# Sheet1.net
KiCad netlist of a schematic drawn in Altium Designer
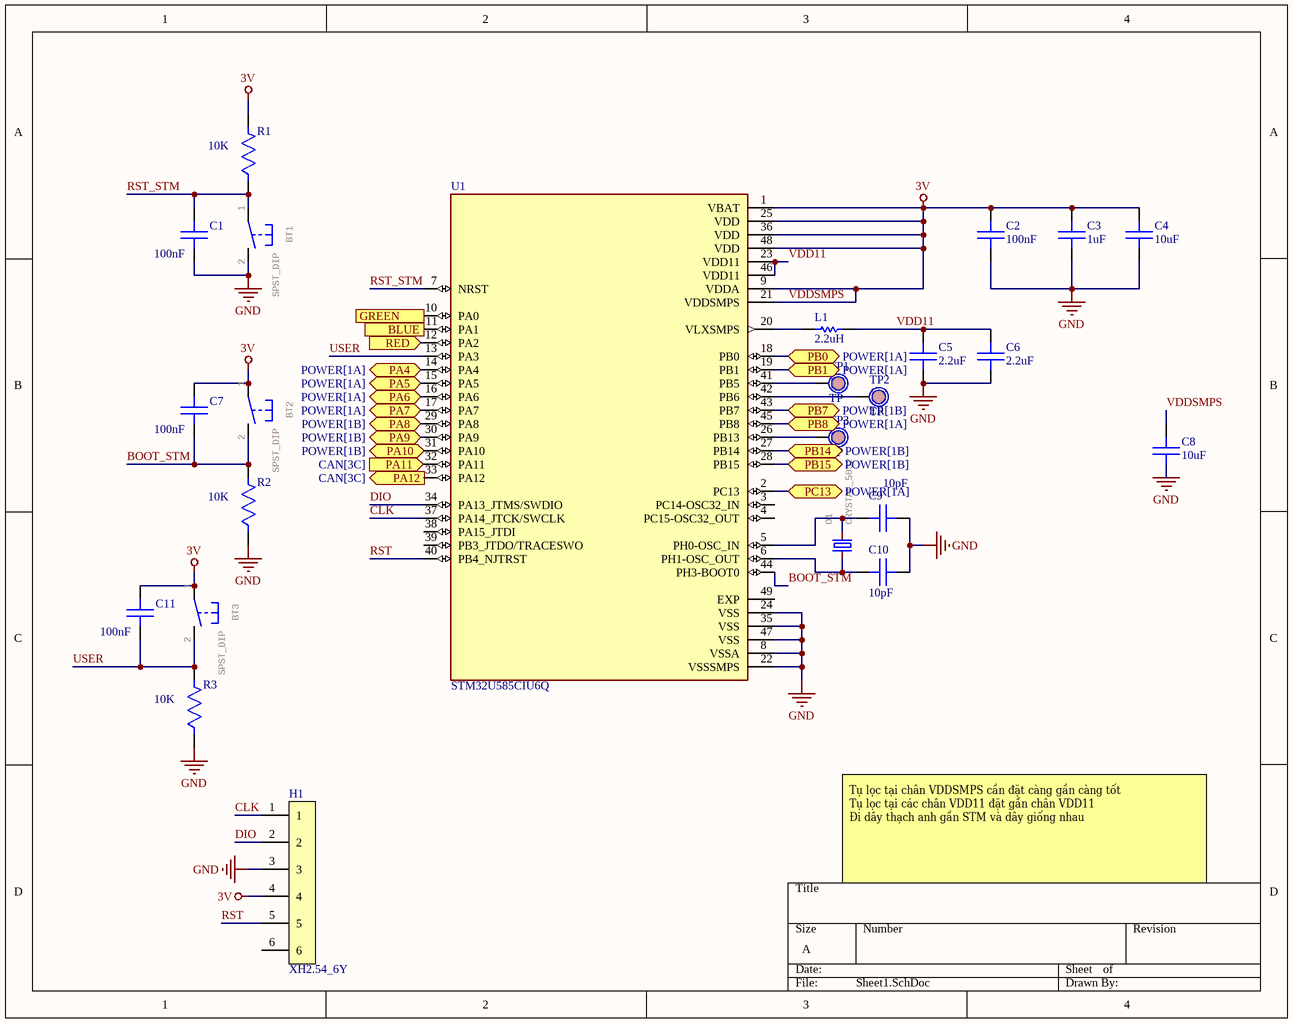
[diagram p0: Sheet1.SchDoc]

(export (version "E")
  (design (tool "Eeschema 10.0.6"))
  (components
    (comp (ref "BT1")
      (value "SPST_DIP")
      (footprint "SPST_BUTTON_2DIP")
      (libsource (lib "IoTVision_Library") (part "SPST_DIP"))
    )
    (comp (ref "BT2")
      (value "SPST_DIP")
      (footprint "SPST_BUTTON_2DIP")
      (libsource (lib "IoTVision_Library") (part "SPST_DIP"))
    )
    (comp (ref "BT3")
      (value "SPST_DIP")
      (footprint "SPST_BUTTON_2DIP")
      (libsource (lib "IoTVision_Library") (part "SPST_DIP"))
    )
    (comp (ref "C1")
      (value "100nF")
      (footprint "C0603")
      (libsource (lib "IoTVision_Library") (part "Capacitor 0603"))
    )
    (comp (ref "C2")
      (value "100nF")
      (footprint "C0603")
      (libsource (lib "IoTVision_Library") (part "Capacitor 0603"))
    )
    (comp (ref "C3")
      (value "1uF")
      (footprint "C0603")
      (libsource (lib "IoTVision_Library") (part "Capacitor 0603"))
    )
    (comp (ref "C4")
      (value "10uF")
      (footprint "C0603")
      (libsource (lib "IoTVision_Library") (part "Capacitor 0603"))
    )
    (comp (ref "C5")
      (value "2.2uF")
      (footprint "C0603")
      (libsource (lib "IoTVision_Library") (part "Capacitor 0603"))
    )
    (comp (ref "C6")
      (value "2.2uF")
      (footprint "C0603")
      (libsource (lib "IoTVision_Library") (part "Capacitor 0603"))
    )
    (comp (ref "C7")
      (value "100nF")
      (footprint "C0603")
      (libsource (lib "IoTVision_Library") (part "Capacitor 0603"))
    )
    (comp (ref "C8")
      (value "10uF")
      (footprint "C0603")
      (libsource (lib "IoTVision_Library") (part "Capacitor 0603"))
    )
    (comp (ref "C9")
      (value "10pF")
      (footprint "C0603")
      (libsource (lib "IoTVision_Library") (part "Capacitor 0603"))
    )
    (comp (ref "C10")
      (value "10pF")
      (footprint "C0603")
      (libsource (lib "IoTVision_Library") (part "Capacitor 0603"))
    )
    (comp (ref "C11")
      (value "100nF")
      (footprint "C0603")
      (libsource (lib "IoTVision_Library") (part "Capacitor 0603"))
    )
    (comp (ref "H1")
      (value "XH2.54_6Y")
      (footprint "JST-XH-06-PACKAGE-LONG-PAD")
      (libsource (lib "Tram_muoi_VietAn") (part "XH2.54_6Y"))
    )
    (comp (ref "L1")
      (value "2.2uH")
      (footprint "Res 1206 SMD")
      (description "RES SMD 5.1 OHM 1% 1/4W 1206")
      (fields
        (field (name "MANUFACTURER") "Yageo")
        (field (name "MANUFACTURER PART NUMBER") "RC1206FR-075R1L")
      )
      (libsource (lib "LPSON") (part "RES-1206"))
    )
    (comp (ref "O1")
      (value "CRYSTAL_5032")
      (footprint "CRYSTAL_5032")
      (libsource (lib "IoTVision_Library") (part "CRYSTAL_5032"))
    )
    (comp (ref "R1")
      (value "10K")
      (footprint "R0603")
      (description "SMD Resistor 0603")
      (fields
        (field (name "MANUFACTURER") "Yageo")
        (field (name "MANUFACTURER PART NUMBER") "RC0603FR-071KL")
      )
      (libsource (lib "IoTVision_Library") (part "Resistor 0603"))
    )
    (comp (ref "R2")
      (value "10K")
      (footprint "R0603")
      (description "SMD Resistor 0603")
      (fields
        (field (name "MANUFACTURER") "Yageo")
        (field (name "MANUFACTURER PART NUMBER") "RC0603FR-071KL")
      )
      (libsource (lib "IoTVision_Library") (part "Resistor 0603"))
    )
    (comp (ref "R3")
      (value "10K")
      (footprint "R0603")
      (description "SMD Resistor 0603")
      (fields
        (field (name "MANUFACTURER") "Yageo")
        (field (name "MANUFACTURER PART NUMBER") "RC0603FR-071KL")
      )
      (libsource (lib "IoTVision_Library") (part "Resistor 0603"))
    )
    (comp (ref "TP1")
      (value "TP")
      (footprint "Test_point_SMD")
      (description "Test Point")
      (libsource (lib "LPSON") (part "Test_point_DNM"))
    )
    (comp (ref "TP2")
      (value "TP")
      (footprint "Test_point_SMD")
      (description "Test Point")
      (libsource (lib "LPSON") (part "Test_point_DNM"))
    )
    (comp (ref "TP3")
      (value "TP")
      (footprint "Test_point_SMD")
      (description "Test Point")
      (libsource (lib "LPSON") (part "Test_point_DNM"))
    )
    (comp (ref "U1")
      (value "STM32U585CIU6Q")
      (footprint "QFN50P700X700X60-49N")
      (fields (field (name "MF") "STMicroelectronics"))
      (libsource (lib "STM32U585CIU6Q") (part "STM32U585CIU6Q"))
    )
  )
  (nets
    (net (code "1") (name "/BLUE") (class "Default")
      (node (ref "U1") (pin "11") (pinfunction "PA1_11") (pintype "bidirectional"))
    )
    (net (code "2") (name "/BOOT_STM") (class "Default")
      (node (ref "BT2") (pin "2") (pinfunction "2_2") (pintype "passive"))
      (node (ref "C7") (pin "1") (pinfunction "1_1") (pintype "passive"))
      (node (ref "R2") (pin "2") (pinfunction "2_2") (pintype "passive"))
      (node (ref "U1") (pin "44") (pinfunction "PH3-BOOT0_44") (pintype "bidirectional"))
    )
    (net (code "3") (name "/CLK") (class "Default")
      (node (ref "H1") (pin "1") (pinfunction "1_1") (pintype "passive"))
      (node (ref "U1") (pin "37") (pinfunction "PA14_JTCK/SWCLK_37") (pintype "bidirectional"))
    )
    (net (code "4") (name "/DIO") (class "Default")
      (node (ref "H1") (pin "2") (pinfunction "2_2") (pintype "passive"))
      (node (ref "U1") (pin "34") (pinfunction "PA13_JTMS/SWDIO_34") (pintype "bidirectional"))
    )
    (net (code "5") (name "/GREEN") (class "Default")
      (node (ref "U1") (pin "10") (pinfunction "PA0_10") (pintype "bidirectional"))
    )
    (net (code "6") (name "/PA4") (class "Default")
      (node (ref "U1") (pin "14") (pinfunction "PA4_14") (pintype "bidirectional"))
    )
    (net (code "7") (name "/PA5") (class "Default")
      (node (ref "U1") (pin "15") (pinfunction "PA5_15") (pintype "bidirectional"))
    )
    (net (code "8") (name "/PA6") (class "Default")
      (node (ref "U1") (pin "16") (pinfunction "PA6_16") (pintype "bidirectional"))
    )
    (net (code "9") (name "/PA7") (class "Default")
      (node (ref "U1") (pin "17") (pinfunction "PA7_17") (pintype "bidirectional"))
    )
    (net (code "10") (name "/PA8") (class "Default")
      (node (ref "U1") (pin "29") (pinfunction "PA8_29") (pintype "bidirectional"))
    )
    (net (code "11") (name "/PA9") (class "Default")
      (node (ref "U1") (pin "30") (pinfunction "PA9_30") (pintype "bidirectional"))
    )
    (net (code "12") (name "/PA10") (class "Default")
      (node (ref "U1") (pin "31") (pinfunction "PA10_31") (pintype "bidirectional"))
    )
    (net (code "13") (name "/PA11") (class "Default")
      (node (ref "U1") (pin "32") (pinfunction "PA11_32") (pintype "bidirectional"))
    )
    (net (code "14") (name "/PA12") (class "Default")
      (node (ref "U1") (pin "33") (pinfunction "PA12_33") (pintype "bidirectional"))
    )
    (net (code "15") (name "/PB0") (class "Default")
      (node (ref "U1") (pin "18") (pinfunction "PB0_18") (pintype "bidirectional"))
    )
    (net (code "16") (name "/PB1") (class "Default")
      (node (ref "U1") (pin "19") (pinfunction "PB1_19") (pintype "bidirectional"))
    )
    (net (code "17") (name "/PB7") (class "Default")
      (node (ref "U1") (pin "43") (pinfunction "PB7_43") (pintype "bidirectional"))
    )
    (net (code "18") (name "/PB8") (class "Default")
      (node (ref "U1") (pin "45") (pinfunction "PB8_45") (pintype "bidirectional"))
    )
    (net (code "19") (name "/PB14") (class "Default")
      (node (ref "U1") (pin "27") (pinfunction "PB14_27") (pintype "bidirectional"))
    )
    (net (code "20") (name "/PB15") (class "Default")
      (node (ref "U1") (pin "28") (pinfunction "PB15_28") (pintype "bidirectional"))
    )
    (net (code "21") (name "/PC13") (class "Default")
      (node (ref "U1") (pin "2") (pinfunction "PC13_2") (pintype "bidirectional"))
    )
    (net (code "22") (name "/RED") (class "Default")
      (node (ref "U1") (pin "12") (pinfunction "PA2_12") (pintype "bidirectional"))
    )
    (net (code "23") (name "/RST") (class "Default")
      (node (ref "H1") (pin "5") (pinfunction "5_5") (pintype "passive"))
      (node (ref "U1") (pin "40") (pinfunction "PB4_NJTRST_40") (pintype "bidirectional"))
    )
    (net (code "24") (name "/RST_STM") (class "Default")
      (node (ref "BT1") (pin "1") (pinfunction "1_1") (pintype "passive"))
      (node (ref "C1") (pin "2") (pinfunction "2_2") (pintype "passive"))
      (node (ref "R1") (pin "1") (pinfunction "1_1") (pintype "passive"))
      (node (ref "U1") (pin "7") (pinfunction "NRST_7") (pintype "bidirectional"))
    )
    (net (code "25") (name "/USER") (class "Default")
      (node (ref "BT3") (pin "2") (pinfunction "2_2") (pintype "passive"))
      (node (ref "C11") (pin "1") (pinfunction "1_1") (pintype "passive"))
      (node (ref "R3") (pin "2") (pinfunction "2_2") (pintype "passive"))
      (node (ref "U1") (pin "13") (pinfunction "PA3_13") (pintype "bidirectional"))
    )
    (net (code "26") (name "/VDD11") (class "Default")
      (node (ref "C5") (pin "2") (pinfunction "2_2") (pintype "passive"))
      (node (ref "C6") (pin "2") (pinfunction "2_2") (pintype "passive"))
      (node (ref "L1") (pin "2") (pinfunction "2_2") (pintype "passive"))
      (node (ref "U1") (pin "23") (pinfunction "VDD11_23") (pintype "power_in"))
      (node (ref "U1") (pin "46") (pinfunction "VDD11_46") (pintype "power_in"))
    )
    (net (code "27") (name "3V") (class "Default")
      (node (ref "BT2") (pin "1") (pinfunction "1_1") (pintype "passive"))
      (node (ref "BT3") (pin "1") (pinfunction "1_1") (pintype "passive"))
      (node (ref "C11") (pin "2") (pinfunction "2_2") (pintype "passive"))
      (node (ref "C2") (pin "2") (pinfunction "2_2") (pintype "passive"))
      (node (ref "C3") (pin "2") (pinfunction "2_2") (pintype "passive"))
      (node (ref "C4") (pin "2") (pinfunction "2_2") (pintype "passive"))
      (node (ref "C7") (pin "2") (pinfunction "2_2") (pintype "passive"))
      (node (ref "C8") (pin "1") (pinfunction "1_1") (pintype "passive"))
      (node (ref "H1") (pin "4") (pinfunction "4_4") (pintype "passive"))
      (node (ref "R1") (pin "2") (pinfunction "2_2") (pintype "passive"))
      (node (ref "U1") (pin "1") (pinfunction "VBAT_1") (pintype "power_in"))
      (node (ref "U1") (pin "21") (pinfunction "VDDSMPS_21") (pintype "power_in"))
      (node (ref "U1") (pin "25") (pinfunction "VDD_25") (pintype "power_in"))
      (node (ref "U1") (pin "36") (pinfunction "VDD_36") (pintype "power_in"))
      (node (ref "U1") (pin "48") (pinfunction "VDD_48") (pintype "power_in"))
      (node (ref "U1") (pin "9") (pinfunction "VDDA_9") (pintype "power_in"))
    )
    (net (code "28") (name "GND") (class "Default")
      (node (ref "BT1") (pin "2") (pinfunction "2_2") (pintype "passive"))
      (node (ref "C1") (pin "1") (pinfunction "1_1") (pintype "passive"))
      (node (ref "C10") (pin "2") (pinfunction "2_2") (pintype "passive"))
      (node (ref "C2") (pin "1") (pinfunction "1_1") (pintype "passive"))
      (node (ref "C3") (pin "1") (pinfunction "1_1") (pintype "passive"))
      (node (ref "C4") (pin "1") (pinfunction "1_1") (pintype "passive"))
      (node (ref "C5") (pin "1") (pinfunction "1_1") (pintype "passive"))
      (node (ref "C6") (pin "1") (pinfunction "1_1") (pintype "passive"))
      (node (ref "C8") (pin "2") (pinfunction "2_2") (pintype "passive"))
      (node (ref "C9") (pin "2") (pinfunction "2_2") (pintype "passive"))
      (node (ref "H1") (pin "3") (pinfunction "3_3") (pintype "passive"))
      (node (ref "R2") (pin "1") (pinfunction "1_1") (pintype "passive"))
      (node (ref "R3") (pin "1") (pinfunction "1_1") (pintype "passive"))
      (node (ref "U1") (pin "22") (pinfunction "VSSSMPS_22") (pintype "power_in"))
      (node (ref "U1") (pin "24") (pinfunction "VSS_24") (pintype "power_in"))
      (node (ref "U1") (pin "35") (pinfunction "VSS_35") (pintype "power_in"))
      (node (ref "U1") (pin "47") (pinfunction "VSS_47") (pintype "power_in"))
      (node (ref "U1") (pin "8") (pinfunction "VSSA_8") (pintype "power_in"))
    )
    (net (code "29") (name "Net-(U1-PB5)") (class "Default")
      (node (ref "TP1") (pin "1") (pinfunction "1_1") (pintype "passive"))
      (node (ref "U1") (pin "41") (pinfunction "PB5_41") (pintype "bidirectional"))
    )
    (net (code "30") (name "Net-(U1-PB6)") (class "Default")
      (node (ref "TP2") (pin "1") (pinfunction "1_1") (pintype "passive"))
      (node (ref "U1") (pin "42") (pinfunction "PB6_42") (pintype "bidirectional"))
    )
    (net (code "31") (name "Net-(U1-PB13)") (class "Default")
      (node (ref "TP3") (pin "1") (pinfunction "1_1") (pintype "passive"))
      (node (ref "U1") (pin "26") (pinfunction "PB13_26") (pintype "bidirectional"))
    )
    (net (code "32") (name "Net-(U1-PH0-OSC_IN)") (class "Default")
      (node (ref "C9") (pin "1") (pinfunction "1_1") (pintype "passive"))
      (node (ref "O1") (pin "2") (pinfunction "2_2") (pintype "passive"))
      (node (ref "U1") (pin "5") (pinfunction "PH0-OSC_IN_5") (pintype "bidirectional"))
    )
    (net (code "33") (name "Net-(U1-PH1-OSC_OUT)") (class "Default")
      (node (ref "C10") (pin "1") (pinfunction "1_1") (pintype "passive"))
      (node (ref "O1") (pin "1") (pinfunction "1_1") (pintype "passive"))
      (node (ref "U1") (pin "6") (pinfunction "PH1-OSC_OUT_6") (pintype "bidirectional"))
    )
    (net (code "34") (name "Net-(U1-VLXSMPS)") (class "Default")
      (node (ref "L1") (pin "1") (pinfunction "1_1") (pintype "passive"))
      (node (ref "U1") (pin "20") (pinfunction "VLXSMPS_20") (pintype "output"))
    )
    (net (code "35") (name "unconnected-(H1-Pad6)") (class "Default")
      (node (ref "H1") (pin "6") (pinfunction "6_6") (pintype "passive"))
    )
    (net (code "36") (name "unconnected-(U1-EXP-Pad49)") (class "Default")
      (node (ref "U1") (pin "49") (pinfunction "EXP_49") (pintype "power_in"))
    )
    (net (code "37") (name "unconnected-(U1-PA15_JTDI-Pad38)") (class "Default")
      (node (ref "U1") (pin "38") (pinfunction "PA15_JTDI_38") (pintype "bidirectional"))
    )
    (net (code "38") (name "unconnected-(U1-PB3_JTDO{slash}TRACESWO-Pad39)") (class "Default")
      (node (ref "U1") (pin "39") (pinfunction "PB3_JTDO/TRACESWO_39") (pintype "bidirectional"))
    )
    (net (code "39") (name "unconnected-(U1-PC14-OSC32_IN-Pad3)") (class "Default")
      (node (ref "U1") (pin "3") (pinfunction "PC14-OSC32_IN_3") (pintype "bidirectional"))
    )
    (net (code "40") (name "unconnected-(U1-PC15-OSC32_OUT-Pad4)") (class "Default")
      (node (ref "U1") (pin "4") (pinfunction "PC15-OSC32_OUT_4") (pintype "bidirectional"))
    )
  )
)
